# MCU.net
KiCad netlist of a schematic drawn in Altium Designer
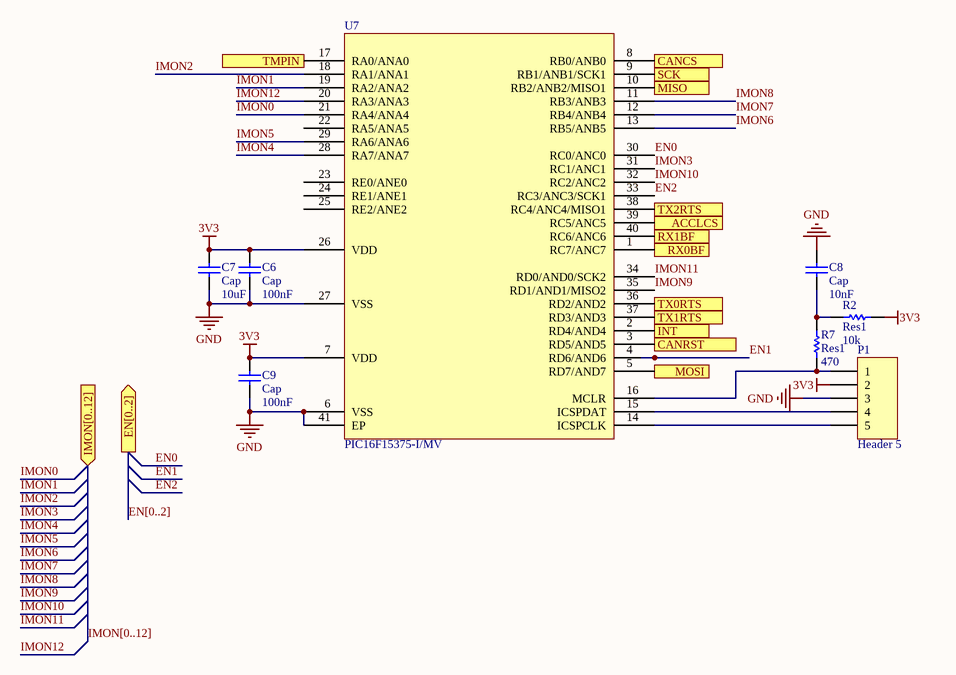
[diagram p0: MCU.SchDoc]

(export (version "E")
  (design (tool "Eeschema 10.0.6"))
  (components
    (comp (ref "C6")
      (value "Cap")
      (footprint "1608[0603]")
      (description "Capacitor")
      (fields (field (name "ALTIUM_VALUE") "100nF") (field (name "PUBLISHER") "Altium Limited"))
      (libsource (lib "Miscellaneous Devices") (part "Cap"))
    )
    (comp (ref "C7")
      (value "Cap")
      (footprint "6-0805_M")
      (description "Capacitor")
      (fields (field (name "ALTIUM_VALUE") "10uF") (field (name "PUBLISHER") "Altium Limited"))
      (libsource (lib "Miscellaneous Devices") (part "Cap"))
    )
    (comp (ref "C8")
      (value "Cap")
      (footprint "1608[0603]")
      (description "Capacitor")
      (fields (field (name "ALTIUM_VALUE") "10nF") (field (name "PUBLISHER") "Altium Limited"))
      (libsource (lib "Miscellaneous Devices") (part "Cap"))
    )
    (comp (ref "C9")
      (value "Cap")
      (footprint "1608[0603]")
      (description "Capacitor")
      (fields (field (name "ALTIUM_VALUE") "100nF") (field (name "PUBLISHER") "Altium Limited"))
      (libsource (lib "Miscellaneous Devices") (part "Cap"))
    )
    (comp (ref "P1")
      (value "Header 5")
      (footprint "HDR1X5")
      (description "Header, 5-Pin")
      (fields (field (name "PUBLISHER") "Altium Limited"))
      (libsource (lib "Miscellaneous Connectors") (part "Header 5"))
    )
    (comp (ref "R2")
      (value "Res1")
      (footprint "0402-A")
      (description "Resistor")
      (fields (field (name "ALTIUM_VALUE") "10k") (field (name "PUBLISHER") "Altium Limited"))
      (libsource (lib "Miscellaneous Devices") (part "Res1"))
    )
    (comp (ref "R7")
      (value "Res1")
      (footprint "0402-A")
      (description "Resistor")
      (fields (field (name "ALTIUM_VALUE") "470") (field (name "PUBLISHER") "Altium Limited"))
      (libsource (lib "Miscellaneous Devices") (part "Res1"))
    )
    (comp (ref "U7")
      (value "PIC16F15375-I/MV")
      (footprint "PIC16F15375-I/MV")
      (libsource (lib "PIC16F15375") (part "PIC16F15375-I/MV"))
    )
  )
  (nets
    (net (code "1") (name "/ACCLCS") (class "Default")
      (node (ref "U7") (pin "39") (pinfunction "RC5/ANC5_39") (pintype "passive"))
    )
    (net (code "2") (name "/CANCS") (class "Default")
      (node (ref "U7") (pin "8") (pinfunction "RB0/ANB0_8") (pintype "passive"))
    )
    (net (code "3") (name "/CANRST") (class "Default")
      (node (ref "U7") (pin "3") (pinfunction "RD5/AND5_3") (pintype "passive"))
    )
    (net (code "4") (name "/EN0") (class "Default")
      (node (ref "U7") (pin "30") (pinfunction "RC0/ANC0_30") (pintype "passive"))
    )
    (net (code "5") (name "/EN1") (class "Default")
      (node (ref "U7") (pin "4") (pinfunction "RD6/AND6_4") (pintype "passive"))
    )
    (net (code "6") (name "/EN2") (class "Default")
      (node (ref "U7") (pin "33") (pinfunction "RC3/ANC3/SCK1_33") (pintype "passive"))
    )
    (net (code "8") (name "/IMON0") (class "Default")
      (node (ref "U7") (pin "21") (pinfunction "RA4/ANA4_21") (pintype "passive"))
    )
    (net (code "9") (name "/IMON1") (class "Default")
      (node (ref "U7") (pin "19") (pinfunction "RA2/ANA2_19") (pintype "passive"))
    )
    (net (code "10") (name "/IMON2") (class "Default")
      (node (ref "U7") (pin "18") (pinfunction "RA1/ANA1_18") (pintype "passive"))
    )
    (net (code "11") (name "/IMON3") (class "Default")
      (node (ref "U7") (pin "31") (pinfunction "RC1/ANC1_31") (pintype "passive"))
    )
    (net (code "12") (name "/IMON4") (class "Default")
      (node (ref "U7") (pin "28") (pinfunction "RA7/ANA7_28") (pintype "passive"))
    )
    (net (code "13") (name "/IMON5") (class "Default")
      (node (ref "U7") (pin "29") (pinfunction "RA6/ANA6_29") (pintype "passive"))
    )
    (net (code "14") (name "/IMON6") (class "Default")
      (node (ref "U7") (pin "13") (pinfunction "RB5/ANB5_13") (pintype "passive"))
    )
    (net (code "15") (name "/IMON7") (class "Default")
      (node (ref "U7") (pin "12") (pinfunction "RB4/ANB4_12") (pintype "passive"))
    )
    (net (code "16") (name "/IMON8") (class "Default")
      (node (ref "U7") (pin "11") (pinfunction "RB3/ANB3_11") (pintype "passive"))
    )
    (net (code "17") (name "/IMON9") (class "Default")
      (node (ref "U7") (pin "35") (pinfunction "RD1/AND1/MISO2_35") (pintype "passive"))
    )
    (net (code "18") (name "/IMON10") (class "Default")
      (node (ref "U7") (pin "32") (pinfunction "RC2/ANC2_32") (pintype "passive"))
    )
    (net (code "19") (name "/IMON11") (class "Default")
      (node (ref "U7") (pin "34") (pinfunction "RD0/AND0/SCK2_34") (pintype "passive"))
    )
    (net (code "20") (name "/IMON12") (class "Default")
      (node (ref "U7") (pin "20") (pinfunction "RA3/ANA3_20") (pintype "passive"))
    )
    (net (code "22") (name "/INT") (class "Default")
      (node (ref "U7") (pin "2") (pinfunction "RD4/AND4_2") (pintype "passive"))
    )
    (net (code "23") (name "/MISO") (class "Default")
      (node (ref "U7") (pin "10") (pinfunction "RB2/ANB2/MISO1_10") (pintype "passive"))
    )
    (net (code "24") (name "/MOSI") (class "Default")
      (node (ref "U7") (pin "5") (pinfunction "RD7/AND7_5") (pintype "passive"))
    )
    (net (code "25") (name "/RX0BF") (class "Default")
      (node (ref "U7") (pin "1") (pinfunction "RC7/ANC7_1") (pintype "passive"))
    )
    (net (code "26") (name "/RX1BF") (class "Default")
      (node (ref "U7") (pin "40") (pinfunction "RC6/ANC6_40") (pintype "passive"))
    )
    (net (code "27") (name "/SCK") (class "Default")
      (node (ref "U7") (pin "9") (pinfunction "RB1/ANB1/SCK1_9") (pintype "passive"))
    )
    (net (code "28") (name "/TMPIN") (class "Default")
      (node (ref "U7") (pin "17") (pinfunction "RA0/ANA0_17") (pintype "passive"))
    )
    (net (code "29") (name "/TX0RTS") (class "Default")
      (node (ref "U7") (pin "36") (pinfunction "RD2/AND2_36") (pintype "passive"))
    )
    (net (code "30") (name "/TX1RTS") (class "Default")
      (node (ref "U7") (pin "37") (pinfunction "RD3/AND3_37") (pintype "passive"))
    )
    (net (code "31") (name "/TX2RTS") (class "Default")
      (node (ref "U7") (pin "38") (pinfunction "RC4/ANC4/MISO1_38") (pintype "passive"))
    )
    (net (code "32") (name "3V3") (class "Default")
      (node (ref "C6") (pin "2") (pinfunction "2_2") (pintype "passive"))
      (node (ref "C7") (pin "2") (pinfunction "2_2") (pintype "passive"))
      (node (ref "C9") (pin "2") (pinfunction "2_2") (pintype "passive"))
      (node (ref "P1") (pin "2") (pinfunction "2_2") (pintype "passive"))
      (node (ref "R2") (pin "2") (pinfunction "2_2") (pintype "passive"))
      (node (ref "U7") (pin "26") (pinfunction "VDD_26") (pintype "passive"))
      (node (ref "U7") (pin "7") (pinfunction "VDD_7") (pintype "passive"))
    )
    (net (code "33") (name "GND") (class "Default")
      (node (ref "C6") (pin "1") (pinfunction "1_1") (pintype "passive"))
      (node (ref "C7") (pin "1") (pinfunction "1_1") (pintype "passive"))
      (node (ref "C8") (pin "1") (pinfunction "1_1") (pintype "passive"))
      (node (ref "C9") (pin "1") (pinfunction "1_1") (pintype "passive"))
      (node (ref "P1") (pin "3") (pinfunction "3_3") (pintype "passive"))
      (node (ref "U7") (pin "27") (pinfunction "VSS_27") (pintype "passive"))
      (node (ref "U7") (pin "41") (pinfunction "EP_41") (pintype "power_in"))
      (node (ref "U7") (pin "6") (pinfunction "VSS_6") (pintype "passive"))
    )
    (net (code "34") (name "Net-(C8-Pad2)") (class "Default")
      (node (ref "C8") (pin "2") (pinfunction "2_2") (pintype "passive"))
      (node (ref "R2") (pin "1") (pinfunction "1_1") (pintype "passive"))
      (node (ref "R7") (pin "2") (pinfunction "2_2") (pintype "passive"))
    )
    (net (code "35") (name "Net-(U7-ICSPCLK)") (class "Default")
      (node (ref "P1") (pin "5") (pinfunction "5_5") (pintype "passive"))
      (node (ref "U7") (pin "14") (pinfunction "ICSPCLK_14") (pintype "passive"))
    )
    (net (code "36") (name "Net-(U7-ICSPDAT)") (class "Default")
      (node (ref "P1") (pin "4") (pinfunction "4_4") (pintype "passive"))
      (node (ref "U7") (pin "15") (pinfunction "ICSPDAT_15") (pintype "passive"))
    )
    (net (code "37") (name "Net-(U7-MCLR)") (class "Default")
      (node (ref "P1") (pin "1") (pinfunction "1_1") (pintype "passive"))
      (node (ref "R7") (pin "1") (pinfunction "1_1") (pintype "passive"))
      (node (ref "U7") (pin "16") (pinfunction "MCLR_16") (pintype "passive"))
    )
    (net (code "38") (name "unconnected-(U7-RA5{slash}ANA5-Pad22)") (class "Default")
      (node (ref "U7") (pin "22") (pinfunction "RA5/ANA5_22") (pintype "passive"))
    )
    (net (code "39") (name "unconnected-(U7-RE0{slash}ANE0-Pad23)") (class "Default")
      (node (ref "U7") (pin "23") (pinfunction "RE0/ANE0_23") (pintype "passive"))
    )
    (net (code "40") (name "unconnected-(U7-RE1{slash}ANE1-Pad24)") (class "Default")
      (node (ref "U7") (pin "24") (pinfunction "RE1/ANE1_24") (pintype "passive"))
    )
    (net (code "41") (name "unconnected-(U7-RE2{slash}ANE2-Pad25)") (class "Default")
      (node (ref "U7") (pin "25") (pinfunction "RE2/ANE2_25") (pintype "passive"))
    )
  )
)
